# LCD.net
KiCad netlist of a schematic drawn in Altium Designer
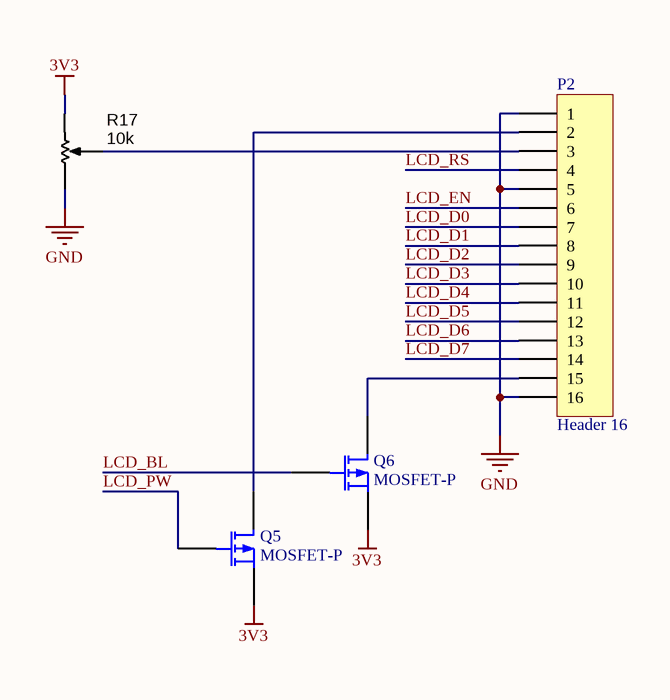
[diagram p0: LCD.SchDoc]

(export (version "E")
  (design (tool "Eeschema 10.0.6"))
  (components
    (comp (ref "P2")
      (value "Header 16")
      (footprint "HDR1X16")
      (description "Header, 16-Pin")
      (fields (field (name "PUBLISHER") "Altium Limited"))
      (libsource (lib "Miscellaneous Connectors") (part "Header 16"))
    )
    (comp (ref "Q5")
      (value "MOSFET-P")
      (footprint "SOT23-3N")
      (description "P-Channel MOSFET")
      (fields (field (name "PUBLISHER") "Altium Limited"))
      (libsource (lib "Schlib1") (part "MOSFET-P"))
    )
    (comp (ref "Q6")
      (value "MOSFET-P")
      (footprint "SOT23-3N")
      (description "P-Channel MOSFET")
      (fields (field (name "PUBLISHER") "Altium Limited"))
      (libsource (lib "Schlib1") (part "MOSFET-P"))
    )
    (comp (ref "R17")
      (value "10k")
      (footprint "RES_TRIMMER_SMD_TC33X1")
      (description "Trimmer SMD 10K 250mW 5-turn Side-adjust")
      (fields (field (name "TOLERANCE") "10%") (field (name "Comment") "RES_TRIMMER_10K_5T_SMD"))
      (libsource (lib "All_Library1") (part "RES_TRIMMER_10K_5T_SMD"))
    )
  )
  (nets
    (net (code "1") (name "/LCD_BL") (class "Default")
      (node (ref "Q6") (pin "1") (pinfunction "G_1") (pintype "passive"))
    )
    (net (code "2") (name "/LCD_D0") (class "Default")
      (node (ref "P2") (pin "7") (pinfunction "7_7") (pintype "passive"))
    )
    (net (code "3") (name "/LCD_D1") (class "Default")
      (node (ref "P2") (pin "8") (pinfunction "8_8") (pintype "passive"))
    )
    (net (code "4") (name "/LCD_D2") (class "Default")
      (node (ref "P2") (pin "9") (pinfunction "9_9") (pintype "passive"))
    )
    (net (code "5") (name "/LCD_D3") (class "Default")
      (node (ref "P2") (pin "10") (pinfunction "10_10") (pintype "passive"))
    )
    (net (code "6") (name "/LCD_D4") (class "Default")
      (node (ref "P2") (pin "11") (pinfunction "11_11") (pintype "passive"))
    )
    (net (code "7") (name "/LCD_D5") (class "Default")
      (node (ref "P2") (pin "12") (pinfunction "12_12") (pintype "passive"))
    )
    (net (code "8") (name "/LCD_D6") (class "Default")
      (node (ref "P2") (pin "13") (pinfunction "13_13") (pintype "passive"))
    )
    (net (code "9") (name "/LCD_D7") (class "Default")
      (node (ref "P2") (pin "14") (pinfunction "14_14") (pintype "passive"))
    )
    (net (code "10") (name "/LCD_EN") (class "Default")
      (node (ref "P2") (pin "6") (pinfunction "6_6") (pintype "passive"))
    )
    (net (code "11") (name "/LCD_PW") (class "Default")
      (node (ref "Q5") (pin "1") (pinfunction "G_1") (pintype "passive"))
    )
    (net (code "12") (name "/LCD_RS") (class "Default")
      (node (ref "P2") (pin "4") (pinfunction "4_4") (pintype "passive"))
    )
    (net (code "13") (name "3V3") (class "Default")
      (node (ref "Q5") (pin "2") (pinfunction "S_2") (pintype "passive"))
      (node (ref "Q6") (pin "2") (pinfunction "S_2") (pintype "passive"))
      (node (ref "R17") (pin "3") (pinfunction "CW_3") (pintype "passive"))
    )
    (net (code "14") (name "GND") (class "Default")
      (node (ref "P2") (pin "1") (pinfunction "1_1") (pintype "passive"))
      (node (ref "P2") (pin "16") (pinfunction "16_16") (pintype "passive"))
      (node (ref "P2") (pin "5") (pinfunction "5_5") (pintype "passive"))
      (node (ref "R17") (pin "1") (pinfunction "CCW_1") (pintype "passive"))
    )
    (net (code "15") (name "Net-(Q5-D)") (class "Default")
      (node (ref "P2") (pin "2") (pinfunction "2_2") (pintype "passive"))
      (node (ref "Q5") (pin "3") (pinfunction "D_3") (pintype "passive"))
    )
    (net (code "16") (name "Net-(Q6-D)") (class "Default")
      (node (ref "P2") (pin "15") (pinfunction "15_15") (pintype "passive"))
      (node (ref "Q6") (pin "3") (pinfunction "D_3") (pintype "passive"))
    )
    (net (code "17") (name "Net-(R17-WIPER)") (class "Default")
      (node (ref "P2") (pin "3") (pinfunction "3_3") (pintype "passive"))
      (node (ref "R17") (pin "2") (pinfunction "WIPER_2") (pintype "passive"))
    )
  )
)
